# PA-HF_100W.net
KiCad netlist of a schematic drawn in Altium Designer
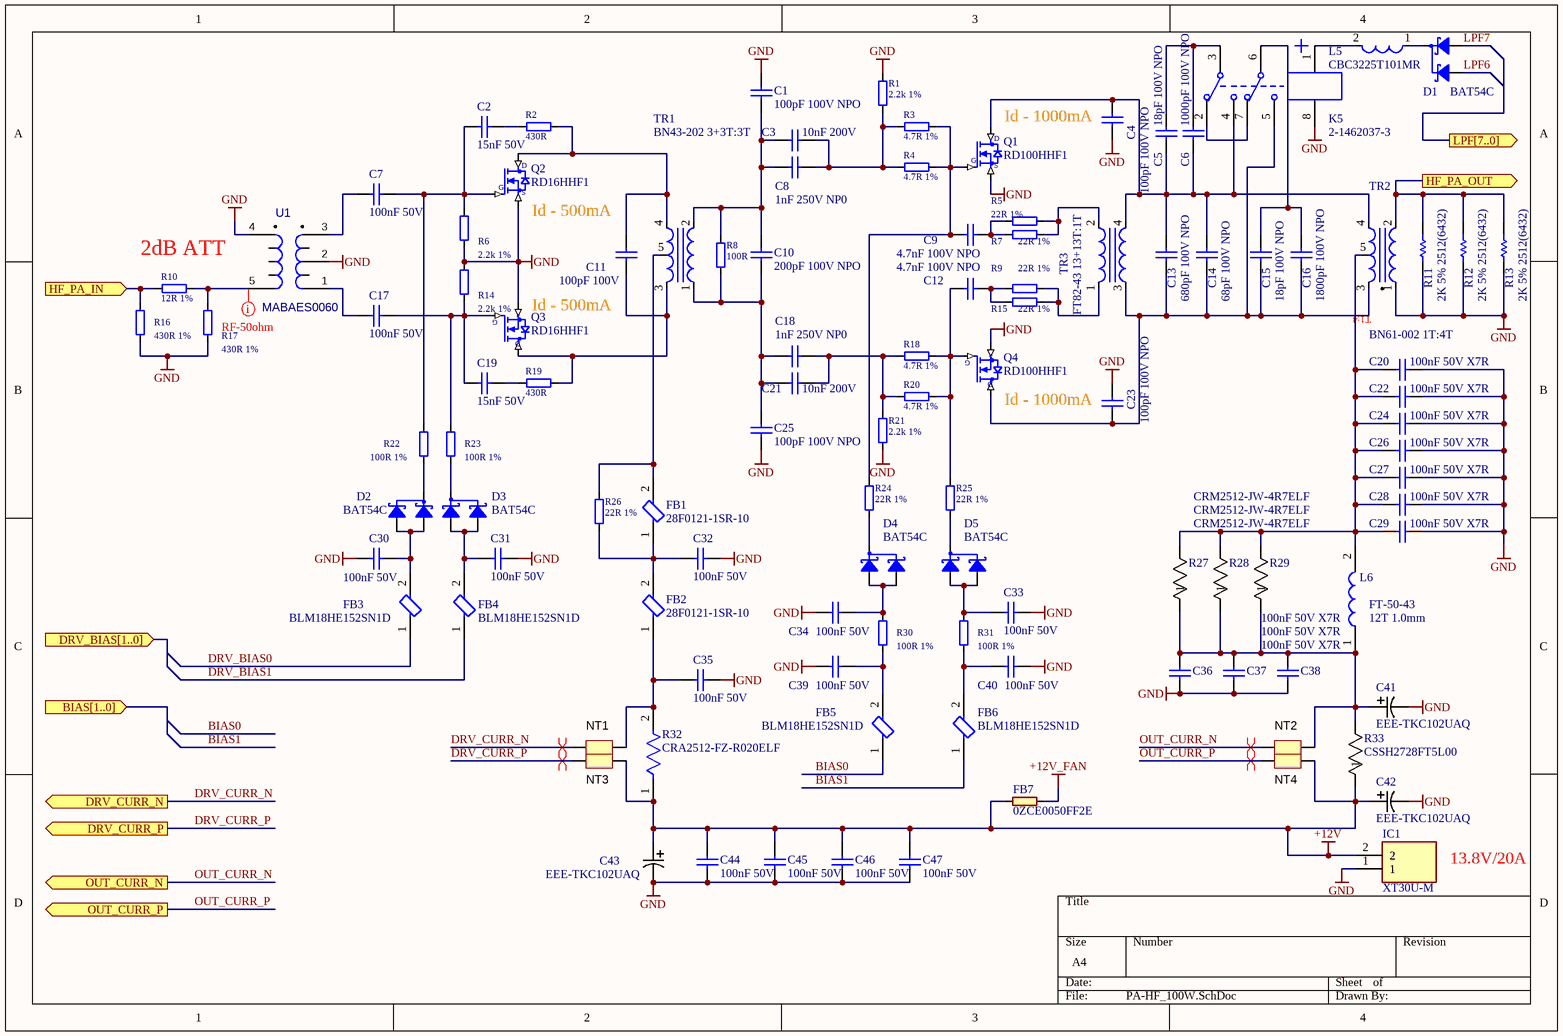
[diagram p0: PA-HF_100W.SchDoc]

(export (version "E")
  (design (tool "Eeschema 10.0.6"))
  (components
    (comp (ref "C1")
      (value "100pF 100V NPO")
      (footprint "C-1206")
      (description "Ceramic Multilayer Capacitor")
      (libsource (lib "Hristo") (part "C semi"))
    )
    (comp (ref "C2")
      (value "15nF 50V")
      (footprint "C-0805")
      (description "Ceramic Multilayer Capacitor")
      (libsource (lib "Hristo") (part "C semi"))
    )
    (comp (ref "C3")
      (value "10nF 200V")
      (footprint "C-1206")
      (description "Ceramic Multilayer Capacitor")
      (libsource (lib "Hristo") (part "C semi"))
    )
    (comp (ref "C4")
      (value "100pF 100V NPO")
      (footprint "C-1206")
      (description "Ceramic Multilayer Capacitor")
      (libsource (lib "Hristo") (part "C semi"))
    )
    (comp (ref "C5")
      (value "18pF 100V NPO")
      (footprint "C-1206")
      (description "Ceramic Multilayer Capacitor")
      (libsource (lib "Hristo") (part "C semi"))
    )
    (comp (ref "C6")
      (value "1000pF 100V NPO")
      (footprint "C-1206")
      (description "Ceramic Multilayer Capacitor")
      (libsource (lib "Hristo") (part "C semi"))
    )
    (comp (ref "C7")
      (value "100nF 50V")
      (footprint "C-0805")
      (description "Ceramic Multilayer Capacitor")
      (libsource (lib "Hristo") (part "C semi"))
    )
    (comp (ref "C8")
      (value "1nF 250V NP0")
      (footprint "C-1206")
      (description "Ceramic Multilayer Capacitor")
      (libsource (lib "Hristo") (part "C semi"))
    )
    (comp (ref "C9")
      (value "4.7nF 100V NPO")
      (footprint "C-1206")
      (description "Ceramic Multilayer Capacitor")
      (libsource (lib "Hristo") (part "C semi"))
    )
    (comp (ref "C10")
      (value "200pF 100V NPO")
      (footprint "C-1206")
      (description "Ceramic Multilayer Capacitor")
      (libsource (lib "Hristo") (part "C semi"))
    )
    (comp (ref "C11")
      (value "100pF 100V")
      (footprint "C-0805")
      (description "Ceramic Multilayer Capacitor")
      (libsource (lib "Hristo") (part "C semi"))
    )
    (comp (ref "C12")
      (value "4.7nF 100V NPO")
      (footprint "C-1206")
      (description "Ceramic Multilayer Capacitor")
      (libsource (lib "Hristo") (part "C semi"))
    )
    (comp (ref "C13")
      (value "680pF 100V NPO")
      (footprint "C-1206")
      (description "Ceramic Multilayer Capacitor")
      (libsource (lib "Hristo") (part "C semi"))
    )
    (comp (ref "C14")
      (value "68pF 100V NPO")
      (footprint "C-1206")
      (description "Ceramic Multilayer Capacitor")
      (libsource (lib "Hristo") (part "C semi"))
    )
    (comp (ref "C15")
      (value "18pF 100V NPO")
      (footprint "C-1206")
      (description "Ceramic Multilayer Capacitor")
      (libsource (lib "Hristo") (part "C semi"))
    )
    (comp (ref "C16")
      (value "1800pF 100V NPO")
      (footprint "C-1206")
      (description "Ceramic Multilayer Capacitor")
      (libsource (lib "Hristo") (part "C semi"))
    )
    (comp (ref "C17")
      (value "100nF 50V")
      (footprint "C-0805")
      (description "Ceramic Multilayer Capacitor")
      (libsource (lib "Hristo") (part "C semi"))
    )
    (comp (ref "C18")
      (value "1nF 250V NP0")
      (footprint "C-1206")
      (description "Ceramic Multilayer Capacitor")
      (libsource (lib "Hristo") (part "C semi"))
    )
    (comp (ref "C19")
      (value "15nF 50V")
      (footprint "C-0805")
      (description "Ceramic Multilayer Capacitor")
      (libsource (lib "Hristo") (part "C semi"))
    )
    (comp (ref "C20")
      (value "100nF 50V X7R")
      (footprint "C-1206")
      (description "Ceramic Multilayer Capacitor")
      (libsource (lib "Hristo") (part "C semi"))
    )
    (comp (ref "C21")
      (value "10nF 200V")
      (footprint "C-1206")
      (description "Ceramic Multilayer Capacitor")
      (libsource (lib "Hristo") (part "C semi"))
    )
    (comp (ref "C22")
      (value "100nF 50V X7R")
      (footprint "C-1206")
      (description "Ceramic Multilayer Capacitor")
      (libsource (lib "Hristo") (part "C semi"))
    )
    (comp (ref "C23")
      (value "100pF 100V NPO")
      (footprint "C-1206")
      (description "Ceramic Multilayer Capacitor")
      (libsource (lib "Hristo") (part "C semi"))
    )
    (comp (ref "C24")
      (value "100nF 50V X7R")
      (footprint "C-1206")
      (description "Ceramic Multilayer Capacitor")
      (libsource (lib "Hristo") (part "C semi"))
    )
    (comp (ref "C25")
      (value "100pF 100V NPO")
      (footprint "C-1206")
      (description "Ceramic Multilayer Capacitor")
      (libsource (lib "Hristo") (part "C semi"))
    )
    (comp (ref "C26")
      (value "100nF 50V X7R")
      (footprint "C-1206")
      (description "Ceramic Multilayer Capacitor")
      (libsource (lib "Hristo") (part "C semi"))
    )
    (comp (ref "C27")
      (value "100nF 50V X7R")
      (footprint "C-1206")
      (description "Ceramic Multilayer Capacitor")
      (libsource (lib "Hristo") (part "C semi"))
    )
    (comp (ref "C28")
      (value "100nF 50V X7R")
      (footprint "C-1206")
      (description "Ceramic Multilayer Capacitor")
      (libsource (lib "Hristo") (part "C semi"))
    )
    (comp (ref "C29")
      (value "100nF 50V X7R")
      (footprint "C-1206")
      (description "Ceramic Multilayer Capacitor")
      (libsource (lib "Hristo") (part "C semi"))
    )
    (comp (ref "C30")
      (value "100nF 50V")
      (footprint "C-0805")
      (description "Ceramic Multilayer Capacitor")
      (libsource (lib "Hristo") (part "C semi"))
    )
    (comp (ref "C31")
      (value "100nF 50V")
      (footprint "C-0805")
      (description "Ceramic Multilayer Capacitor")
      (libsource (lib "Hristo") (part "C semi"))
    )
    (comp (ref "C32")
      (value "100nF 50V")
      (footprint "C-0805")
      (description "Ceramic Multilayer Capacitor")
      (libsource (lib "Hristo") (part "C semi"))
    )
    (comp (ref "C33")
      (value "100nF 50V")
      (footprint "C-0805")
      (description "Ceramic Multilayer Capacitor")
      (libsource (lib "Hristo") (part "C semi"))
    )
    (comp (ref "C34")
      (value "100nF 50V")
      (footprint "C-0805")
      (description "Ceramic Multilayer Capacitor")
      (libsource (lib "Hristo") (part "C semi"))
    )
    (comp (ref "C35")
      (value "100nF 50V")
      (footprint "C-0805")
      (description "Ceramic Multilayer Capacitor")
      (libsource (lib "Hristo") (part "C semi"))
    )
    (comp (ref "C36")
      (value "100nF 50V X7R")
      (footprint "C-1206")
      (description "Ceramic Multilayer Capacitor")
      (libsource (lib "Hristo") (part "C semi"))
    )
    (comp (ref "C37")
      (value "100nF 50V X7R")
      (footprint "C-1206")
      (description "Ceramic Multilayer Capacitor")
      (libsource (lib "Hristo") (part "C semi"))
    )
    (comp (ref "C38")
      (value "100nF 50V X7R")
      (footprint "C-1206")
      (description "Ceramic Multilayer Capacitor")
      (libsource (lib "Hristo") (part "C semi"))
    )
    (comp (ref "C39")
      (value "100nF 50V")
      (footprint "C-0805")
      (description "Ceramic Multilayer Capacitor")
      (libsource (lib "Hristo") (part "C semi"))
    )
    (comp (ref "C40")
      (value "100nF 50V")
      (footprint "C-0805")
      (description "Ceramic Multilayer Capacitor")
      (libsource (lib "Hristo") (part "C semi"))
    )
    (comp (ref "C41")
      (value "EEE-TKC102UAQ")
      (footprint "CAP_PAN_EEE_H13_PAN")
      (description "No Description Available")
      (fields (field (name "COPYRIGHT") "Copyright (C) 2022 Ultra Librarian. All rights reserved."))
      (libsource (lib "Hristo") (part "EEE-TKC102UAQ"))
    )
    (comp (ref "C42")
      (value "EEE-TKC102UAQ")
      (footprint "CAP_PAN_EEE_H13_PAN")
      (description "No Description Available")
      (fields (field (name "COPYRIGHT") "Copyright (C) 2022 Ultra Librarian. All rights reserved."))
      (libsource (lib "Hristo") (part "EEE-TKC102UAQ"))
    )
    (comp (ref "C43")
      (value "EEE-TKC102UAQ")
      (footprint "CAP_PAN_EEE_H13_PAN")
      (description "No Description Available")
      (fields (field (name "COPYRIGHT") "Copyright (C) 2022 Ultra Librarian. All rights reserved."))
      (libsource (lib "Hristo") (part "EEE-TKC102UAQ"))
    )
    (comp (ref "C44")
      (value "100nF 50V")
      (footprint "C-0805")
      (description "Ceramic Multilayer Capacitor")
      (libsource (lib "Hristo") (part "C semi"))
    )
    (comp (ref "C45")
      (value "100nF 50V")
      (footprint "C-0805")
      (description "Ceramic Multilayer Capacitor")
      (libsource (lib "Hristo") (part "C semi"))
    )
    (comp (ref "C46")
      (value "100nF 50V")
      (footprint "C-0805")
      (description "Ceramic Multilayer Capacitor")
      (libsource (lib "Hristo") (part "C semi"))
    )
    (comp (ref "C47")
      (value "100nF 50V")
      (footprint "C-0805")
      (description "Ceramic Multilayer Capacitor")
      (libsource (lib "Hristo") (part "C semi"))
    )
    (comp (ref "D1")
      (value "BAT54C")
      (footprint "SOT-23")
      (description "Schottky barrier diodes")
      (fields (field (name "MANUFACTURER") "NXP"))
      (libsource (lib "EXP-SX Power R2.4") (part "D SH SOT23C"))
    )
    (comp (ref "D2")
      (value "BAT54C")
      (footprint "SOT-23")
      (description "Schottky barrier diodes")
      (fields (field (name "MANUFACTURER") "NXP"))
      (libsource (lib "EXP-SX Power R2.4") (part "D SH SOT23C"))
    )
    (comp (ref "D3")
      (value "BAT54C")
      (footprint "SOT-23")
      (description "Schottky barrier diodes")
      (fields (field (name "MANUFACTURER") "NXP"))
      (libsource (lib "EXP-SX Power R2.4") (part "D SH SOT23C"))
    )
    (comp (ref "D4")
      (value "BAT54C")
      (footprint "SOT-23")
      (description "Schottky barrier diodes")
      (fields (field (name "MANUFACTURER") "NXP"))
      (libsource (lib "EXP-SX Power R2.4") (part "D SH SOT23C"))
    )
    (comp (ref "D5")
      (value "BAT54C")
      (footprint "SOT-23")
      (description "Schottky barrier diodes")
      (fields (field (name "MANUFACTURER") "NXP"))
      (libsource (lib "EXP-SX Power R2.4") (part "D SH SOT23C"))
    )
    (comp (ref "FB1")
      (value "28F0121-1SR-10")
      (footprint "FP-28F0121-1SR-10-MFG")
      (description "FERRITE BEAD 96 OHM 2SMD 1LN")
      (libsource (lib "Altium Content Vault") (part "5f30dd21d616792df468990f7003faa"))
    )
    (comp (ref "FB2")
      (value "28F0121-1SR-10")
      (footprint "FP-28F0121-1SR-10-MFG")
      (description "FERRITE BEAD 96 OHM 2SMD 1LN")
      (libsource (lib "Altium Content Vault") (part "5f30dd21d616792df468990f7003faa"))
    )
    (comp (ref "FB3")
      (value "BLM18HE152SN1D")
      (footprint "FP-BLM18-0_15-t0_8-IPC_C")
      (description "Chip Ferrite Bead, 0603, 1500Ω @ 100MHz, 0.5Ω, 25%, 500mA")
      (fields (field (name "TOLERANCE") "25%"))
      (libsource (lib "Altium Content Vault") (part "5f30dd21d616792df468990f7003faa"))
    )
    (comp (ref "FB4")
      (value "BLM18HE152SN1D")
      (footprint "FP-BLM18-0_15-t0_8-IPC_C")
      (description "Chip Ferrite Bead, 0603, 1500Ω @ 100MHz, 0.5Ω, 25%, 500mA")
      (fields (field (name "TOLERANCE") "25%"))
      (libsource (lib "Altium Content Vault") (part "5f30dd21d616792df468990f7003faa"))
    )
    (comp (ref "FB5")
      (value "BLM18HE152SN1D")
      (footprint "FP-BLM18-0_15-t0_8-IPC_C")
      (description "Chip Ferrite Bead, 0603, 1500Ω @ 100MHz, 0.5Ω, 25%, 500mA")
      (fields (field (name "TOLERANCE") "25%"))
      (libsource (lib "Altium Content Vault") (part "5f30dd21d616792df468990f7003faa"))
    )
    (comp (ref "FB6")
      (value "BLM18HE152SN1D")
      (footprint "FP-BLM18-0_15-t0_8-IPC_C")
      (description "Chip Ferrite Bead, 0603, 1500Ω @ 100MHz, 0.5Ω, 25%, 500mA")
      (fields (field (name "TOLERANCE") "25%"))
      (libsource (lib "Altium Content Vault") (part "5f30dd21d616792df468990f7003faa"))
    )
    (comp (ref "FB7")
      (value "0ZCE0050FF2E")
      (footprint "C-0805")
      (description "Chip Ferrite Bead")
      (fields (field (name "MANUFACTURER") "KING CORE"))
      (libsource (lib "Hristo") (part "L BEAD SMD"))
    )
    (comp (ref "IC1")
      (value "XT30U-M")
      (footprint "SamacSys:XT30UM")
      (description "Integrated Circuit")
      (libsource (lib "*") (part "XT30U-M"))
    )
    (comp (ref "K5")
      (value "2-1462037-3")
      (footprint "TECO-2-1462037-3_V")
      (description "Signal Relay, 2 A, 12 VDC, -40 to 85 degC, 8-Pin SMD, RoHS, Tape and Reel")
      (fields (field (name "MANUFACTURER") "TE Connectivity"))
      (libsource (lib "Hristo") (part "CMP-2000-05409-1"))
    )
    (comp (ref "L5")
      (value "CBC3225T101MR")
      (footprint "FP-CB3225-MFG")
      (description "SMD Inductors 100uH ±20% 0.34A 1.82Ω 1210")
      (fields (field (name "TOLERANCE") "20%"))
      (libsource (lib "Altium Content Vault") (part "725321dda6339637d4d059423bc1c3c"))
    )
    (comp (ref "L6")
      (value "FT-50-43")
      (footprint "Amidon_FT50_43")
      (fields (field (name "ALTIUM_VALUE") "12T 1.0mm"))
      (libsource (lib "Hristo") (part "Amidon"))
    )
    (comp (ref "NT1")
      (value "Net-Tie")
      (footprint "Net-Tie_10mil")
      (description "Single point connection between nets.")
      (fields (field (name "SYMBOLCREATOR") "codlsc") (field (name "PUBLISHER") "Texas Instruments"))
      (libsource (lib "Hristo") (part "Net-Tie"))
    )
    (comp (ref "NT2")
      (value "Net-Tie")
      (footprint "Net-Tie_10mil")
      (description "Single point connection between nets.")
      (fields (field (name "SYMBOLCREATOR") "codlsc") (field (name "PUBLISHER") "Texas Instruments"))
      (libsource (lib "Hristo") (part "Net-Tie"))
    )
    (comp (ref "NT3")
      (value "Net-Tie")
      (footprint "Net-Tie_10mil")
      (description "Single point connection between nets.")
      (fields (field (name "SYMBOLCREATOR") "codlsc") (field (name "PUBLISHER") "Texas Instruments"))
      (libsource (lib "Hristo") (part "Net-Tie"))
    )
    (comp (ref "NT4")
      (value "Net-Tie")
      (footprint "Net-Tie_10mil")
      (description "Single point connection between nets.")
      (fields (field (name "SYMBOLCREATOR") "codlsc") (field (name "PUBLISHER") "Texas Instruments"))
      (libsource (lib "Hristo") (part "Net-Tie"))
    )
    (comp (ref "Q1")
      (value "RD100HHF1")
      (footprint "RD100HHF1")
      (libsource (lib "Hristo") (part "RD100HHF1"))
    )
    (comp (ref "Q2") (value "RD16HHF1") (footprint "RD16HHF1") (libsource (lib "Hristo") (part "RD16HHF1")))
    (comp (ref "Q3") (value "RD16HHF1") (footprint "RD16HHF1") (libsource (lib "Hristo") (part "RD16HHF1")))
    (comp (ref "Q4")
      (value "RD100HHF1")
      (footprint "RD100HHF1")
      (libsource (lib "Hristo") (part "RD100HHF1"))
    )
    (comp (ref "R1")
      (value "2.2k 1%")
      (footprint "R-1206")
      (description "Chip Resistor")
      (libsource (lib "Hristo") (part "RES semi"))
    )
    (comp (ref "R2")
      (value "430R")
      (footprint "R-1206")
      (description "Chip Resistor")
      (libsource (lib "Hristo") (part "RES semi"))
    )
    (comp (ref "R3")
      (value "4.7R 1%")
      (footprint "R-1206")
      (description "Chip Resistor")
      (libsource (lib "Hristo") (part "RES semi"))
    )
    (comp (ref "R4")
      (value "4.7R 1%")
      (footprint "R-1206")
      (description "Chip Resistor")
      (libsource (lib "Hristo") (part "RES semi"))
    )
    (comp (ref "R5")
      (value "22R 1%")
      (footprint "R-1206")
      (description "Chip Resistor")
      (libsource (lib "Hristo") (part "RES semi"))
    )
    (comp (ref "R6")
      (value "2.2k 1%")
      (footprint "R-0805")
      (description "Chip Resistor")
      (libsource (lib "Hristo") (part "RES semi"))
    )
    (comp (ref "R7")
      (value "22R 1%")
      (footprint "R-1206")
      (description "Chip Resistor")
      (libsource (lib "Hristo") (part "RES semi"))
    )
    (comp (ref "R8")
      (value "100R")
      (footprint "R-1206")
      (description "Chip Resistor")
      (libsource (lib "Hristo") (part "RES semi"))
    )
    (comp (ref "R9")
      (value "22R 1%")
      (footprint "R-1206")
      (description "Chip Resistor")
      (libsource (lib "Hristo") (part "RES semi"))
    )
    (comp (ref "R10")
      (value "12R 1%")
      (footprint "R-0805")
      (description "Chip Resistor")
      (libsource (lib "Hristo") (part "RES semi"))
    )
    (comp (ref "R11")
      (value "2K 5% 2512(6432)")
      (footprint "RESC2512(6432)_N")
      (description "2K 1W 5% 2512 (6432 Metric)  SMD")
      (fields (field (name "POWER") "1 W") (field (name "TOLERANCE") "5 %"))
      (libsource (lib "Altium Content Vault") (part "RES"))
    )
    (comp (ref "R12")
      (value "2K 5% 2512(6432)")
      (footprint "RESC2512(6432)_N")
      (description "2K 1W 5% 2512 (6432 Metric)  SMD")
      (fields (field (name "POWER") "1 W") (field (name "TOLERANCE") "5 %"))
      (libsource (lib "Altium Content Vault") (part "RES"))
    )
    (comp (ref "R13")
      (value "2K 5% 2512(6432)")
      (footprint "RESC2512(6432)_N")
      (description "2K 1W 5% 2512 (6432 Metric)  SMD")
      (fields (field (name "POWER") "1 W") (field (name "TOLERANCE") "5 %"))
      (libsource (lib "Altium Content Vault") (part "RES"))
    )
    (comp (ref "R14")
      (value "2.2k 1%")
      (footprint "R-0805")
      (description "Chip Resistor")
      (libsource (lib "Hristo") (part "RES semi"))
    )
    (comp (ref "R15")
      (value "22R 1%")
      (footprint "R-1206")
      (description "Chip Resistor")
      (libsource (lib "Hristo") (part "RES semi"))
    )
    (comp (ref "R16")
      (value "430R 1%")
      (footprint "R-0805")
      (description "Chip Resistor")
      (libsource (lib "Hristo") (part "RES semi"))
    )
    (comp (ref "R17")
      (value "430R 1%")
      (footprint "R-0805")
      (description "Chip Resistor")
      (libsource (lib "Hristo") (part "RES semi"))
    )
    (comp (ref "R18")
      (value "4.7R 1%")
      (footprint "R-1206")
      (description "Chip Resistor")
      (libsource (lib "Hristo") (part "RES semi"))
    )
    (comp (ref "R19")
      (value "430R")
      (footprint "R-1206")
      (description "Chip Resistor")
      (libsource (lib "Hristo") (part "RES semi"))
    )
    (comp (ref "R20")
      (value "4.7R 1%")
      (footprint "R-1206")
      (description "Chip Resistor")
      (libsource (lib "Hristo") (part "RES semi"))
    )
    (comp (ref "R21")
      (value "2.2k 1%")
      (footprint "R-1206")
      (description "Chip Resistor")
      (libsource (lib "Hristo") (part "RES semi"))
    )
    (comp (ref "R22")
      (value "100R 1%")
      (footprint "R-0805")
      (description "Chip Resistor")
      (libsource (lib "Hristo") (part "RES semi"))
    )
    (comp (ref "R23")
      (value "100R 1%")
      (footprint "R-0805")
      (description "Chip Resistor")
      (libsource (lib "Hristo") (part "RES semi"))
    )
    (comp (ref "R24")
      (value "22R 1%")
      (footprint "R-1206")
      (description "Chip Resistor")
      (libsource (lib "Hristo") (part "RES semi"))
    )
    (comp (ref "R25")
      (value "22R 1%")
      (footprint "R-1206")
      (description "Chip Resistor")
      (libsource (lib "Hristo") (part "RES semi"))
    )
    (comp (ref "R26")
      (value "22R 1%")
      (footprint "R-1206")
      (description "Chip Resistor")
      (libsource (lib "Hristo") (part "RES semi"))
    )
    (comp (ref "R27")
      (value "CRM2512-JW-4R7ELF")
      (footprint "BO_CR2512")
      (description "No Description Available")
      (fields (field (name "COPYRIGHT") "Copyright (C) 2022 Ultra Librarian. All rights reserved."))
      (libsource (lib "Hristo") (part "CRM2512-JW-4R7ELF"))
    )
    (comp (ref "R28")
      (value "CRM2512-JW-4R7ELF")
      (footprint "BO_CR2512")
      (description "No Description Available")
      (fields (field (name "COPYRIGHT") "Copyright (C) 2022 Ultra Librarian. All rights reserved."))
      (libsource (lib "Hristo") (part "CRM2512-JW-4R7ELF"))
    )
    (comp (ref "R29")
      (value "CRM2512-JW-4R7ELF")
      (footprint "BO_CR2512")
      (description "No Description Available")
      (fields (field (name "COPYRIGHT") "Copyright (C) 2022 Ultra Librarian. All rights reserved."))
      (libsource (lib "Hristo") (part "CRM2512-JW-4R7ELF"))
    )
    (comp (ref "R30")
      (value "100R 1%")
      (footprint "R-0805")
      (description "Chip Resistor")
      (libsource (lib "Hristo") (part "RES semi"))
    )
    (comp (ref "R31")
      (value "100R 1%")
      (footprint "R-0805")
      (description "Chip Resistor")
      (libsource (lib "Hristo") (part "RES semi"))
    )
    (comp (ref "R32")
      (value "CRA2512-FZ-R020ELF")
      (footprint "FP-CRA2512-IPC_C")
      (description "RES 0.02 OHM 1% 3W 2512")
      (libsource (lib "Altium Content Vault") (part "1029c3af85768c4190bb7ad29bc67b5"))
    )
    (comp (ref "R33")
      (value "CSSH2728FT5L00")
      (footprint "STA_CSSH2728_STP")
      (description "No Description Available")
      (fields (field (name "COPYRIGHT") "Copyright (C) 2022 Ultra Librarian. All rights reserved."))
      (libsource (lib "Hristo") (part "CSSH2728FT5L00"))
    )
    (comp (ref "TR1")
      (value "BN43-202 3+3T:3T")
      (footprint "BN43-202")
      (description "BN43-202 3+3T:3T 0.5mm")
      (libsource (lib "Sch") (part "BN43-202 3+3T{colon}3T"))
    )
    (comp (ref "TR2")
      (value "BN61-002 1T:4T")
      (footprint "BN61-002")
      (description "BN61-002 1T:4T 25ohms coaxial")
      (libsource (lib "Hristo") (part "BN61-002 1T{colon}4T"))
    )
    (comp (ref "TR3")
      (value "FT82-43 13+13T:1T")
      (footprint "Amidon_FT82-43")
      (description "BN43-202 3+3T:3T 0.5mm")
      (libsource (lib "Hristo") (part "FT82-43 13+13T{colon}1T"))
    )
    (comp (ref "U1")
      (value "MABAES0060")
      (footprint "TRANSF_ACORE2")
      (description "1:1")
      (libsource (lib "Hristo") (part "MABAES0060"))
    )
  )
  (nets
    (net (code "7") (name "+12V") (class "Default")
      (node (ref "C42") (pin "1") (pinfunction "1_1") (pintype "passive"))
      (node (ref "C43") (pin "1") (pinfunction "1_1") (pintype "passive"))
      (node (ref "C44") (pin "2") (pinfunction "2_2") (pintype "passive"))
      (node (ref "C45") (pin "2") (pinfunction "2_2") (pintype "passive"))
      (node (ref "C46") (pin "2") (pinfunction "2_2") (pintype "passive"))
      (node (ref "C47") (pin "2") (pinfunction "2_2") (pintype "passive"))
      (node (ref "FB7") (pin "1") (pinfunction "1_1") (pintype "passive"))
      (node (ref "IC1") (pin "2") (pinfunction "2_2") (pintype "passive"))
      (node (ref "NT3") (pin "2") (pinfunction "2_2") (pintype "passive"))
      (node (ref "NT4") (pin "2") (pinfunction "2_2") (pintype "passive"))
      (node (ref "R32") (pin "1") (pinfunction "1_1") (pintype "passive"))
      (node (ref "R33") (pin "1") (pinfunction "1_1") (pintype "passive"))
    )
    (net (code "8") (name "+12V_FAN") (class "Default")
      (node (ref "FB7") (pin "2") (pinfunction "2_2") (pintype "passive"))
    )
    (net (code "9") (name "/BIAS0") (class "Default")
      (node (ref "FB5") (pin "1") (pinfunction "1_1") (pintype "passive"))
    )
    (net (code "10") (name "/BIAS1") (class "Default")
      (node (ref "FB6") (pin "1") (pinfunction "1_1") (pintype "passive"))
    )
    (net (code "12") (name "/DRV_BIAS0") (class "Default")
      (node (ref "FB3") (pin "1") (pinfunction "1_1") (pintype "passive"))
    )
    (net (code "13") (name "/DRV_BIAS1") (class "Default")
      (node (ref "FB4") (pin "1") (pinfunction "1_1") (pintype "passive"))
    )
    (net (code "15") (name "/DRV_CURR_N") (class "Default")
      (node (ref "NT1") (pin "1") (pinfunction "1_1") (pintype "passive"))
    )
    (net (code "16") (name "/DRV_CURR_P") (class "Default")
      (node (ref "NT3") (pin "1") (pinfunction "1_1") (pintype "passive"))
    )
    (net (code "17") (name "/HF_PA_IN") (class "Default")
      (node (ref "R10") (pin "1") (pinfunction "1_1") (pintype "passive"))
      (node (ref "R16") (pin "2") (pinfunction "2_2") (pintype "passive"))
    )
    (net (code "18") (name "/HF_PA_OUT") (class "Default")
      (node (ref "R11") (pin "2") (pinfunction "2_2") (pintype "passive"))
      (node (ref "R12") (pin "2") (pinfunction "2_2") (pintype "passive"))
      (node (ref "R13") (pin "2") (pinfunction "2_2") (pintype "passive"))
      (node (ref "TR2") (pin "2") (pinfunction "2_2") (pintype "passive"))
    )
    (net (code "19") (name "/LPF6") (class "Default") (node (ref "D1") (pin "2") (pintype "passive")))
    (net (code "20") (name "/LPF7") (class "Default") (node (ref "D1") (pin "1") (pintype "passive")))
    (net (code "22") (name "/OUT_CURR_N") (class "Default")
      (node (ref "NT2") (pin "1") (pinfunction "1_1") (pintype "passive"))
    )
    (net (code "23") (name "/OUT_CURR_P") (class "Default")
      (node (ref "NT4") (pin "1") (pinfunction "1_1") (pintype "passive"))
    )
    (net (code "24") (name "GND") (class "Default")
      (node (ref "C1") (pin "1") (pinfunction "1_1") (pintype "passive"))
      (node (ref "C20") (pin "1") (pinfunction "1_1") (pintype "passive"))
      (node (ref "C22") (pin "1") (pinfunction "1_1") (pintype "passive"))
      (node (ref "C23") (pin "1") (pinfunction "1_1") (pintype "passive"))
      (node (ref "C24") (pin "1") (pinfunction "1_1") (pintype "passive"))
      (node (ref "C25") (pin "2") (pinfunction "2_2") (pintype "passive"))
      (node (ref "C26") (pin "1") (pinfunction "1_1") (pintype "passive"))
      (node (ref "C27") (pin "1") (pinfunction "1_1") (pintype "passive"))
      (node (ref "C28") (pin "1") (pinfunction "1_1") (pintype "passive"))
      (node (ref "C29") (pin "1") (pinfunction "1_1") (pintype "passive"))
      (node (ref "C30") (pin "2") (pinfunction "2_2") (pintype "passive"))
      (node (ref "C31") (pin "1") (pinfunction "1_1") (pintype "passive"))
      (node (ref "C32") (pin "1") (pinfunction "1_1") (pintype "passive"))
      (node (ref "C33") (pin "1") (pinfunction "1_1") (pintype "passive"))
      (node (ref "C34") (pin "1") (pinfunction "1_1") (pintype "passive"))
      (node (ref "C35") (pin "1") (pinfunction "1_1") (pintype "passive"))
      (node (ref "C36") (pin "1") (pinfunction "1_1") (pintype "passive"))
      (node (ref "C37") (pin "1") (pinfunction "1_1") (pintype "passive"))
      (node (ref "C38") (pin "1") (pinfunction "1_1") (pintype "passive"))
      (node (ref "C39") (pin "1") (pinfunction "1_1") (pintype "passive"))
      (node (ref "C4") (pin "2") (pinfunction "2_2") (pintype "passive"))
      (node (ref "C40") (pin "1") (pinfunction "1_1") (pintype "passive"))
      (node (ref "C41") (pin "2") (pinfunction "2_2") (pintype "passive"))
      (node (ref "C42") (pin "2") (pinfunction "2_2") (pintype "passive"))
      (node (ref "C43") (pin "2") (pinfunction "2_2") (pintype "passive"))
      (node (ref "C44") (pin "1") (pinfunction "1_1") (pintype "passive"))
      (node (ref "C45") (pin "1") (pinfunction "1_1") (pintype "passive"))
      (node (ref "C46") (pin "1") (pinfunction "1_1") (pintype "passive"))
      (node (ref "C47") (pin "1") (pinfunction "1_1") (pintype "passive"))
      (node (ref "IC1") (pin "1") (pinfunction "1_1") (pintype "passive"))
      (node (ref "K5") (pin "8") (pinfunction "8_8") (pintype "passive"))
      (node (ref "Q1") (pin "1") (pinfunction "S_1") (pintype "input"))
      (node (ref "Q2") (pin "1") (pinfunction "S_1") (pintype "input"))
      (node (ref "Q3") (pin "1") (pinfunction "S_1") (pintype "input"))
      (node (ref "Q4") (pin "1") (pinfunction "S_1") (pintype "input"))
      (node (ref "R1") (pin "2") (pinfunction "2_2") (pintype "passive"))
      (node (ref "R11") (pin "1") (pinfunction "1_1") (pintype "passive"))
      (node (ref "R12") (pin "1") (pinfunction "1_1") (pintype "passive"))
      (node (ref "R13") (pin "1") (pinfunction "1_1") (pintype "passive"))
      (node (ref "R14") (pin "2") (pinfunction "2_2") (pintype "passive"))
      (node (ref "R16") (pin "1") (pinfunction "1_1") (pintype "passive"))
      (node (ref "R17") (pin "1") (pinfunction "1_1") (pintype "passive"))
      (node (ref "R21") (pin "2") (pinfunction "2_2") (pintype "passive"))
      (node (ref "R6") (pin "1") (pinfunction "1_1") (pintype "passive"))
      (node (ref "TR2") (pin "1") (pinfunction "1_1") (pintype "passive"))
      (node (ref "U1") (pin "2") (pinfunction "S2_2") (pintype "passive"))
      (node (ref "U1") (pin "4") (pinfunction "P1_4") (pintype "passive"))
    )
    (net (code "25") (name "Net-(C1-Pad2)") (class "Default")
      (node (ref "C1") (pin "2") (pinfunction "2_2") (pintype "passive"))
      (node (ref "C10") (pin "1") (pinfunction "1_1") (pintype "passive"))
      (node (ref "C3") (pin "1") (pinfunction "1_1") (pintype "passive"))
      (node (ref "C8") (pin "1") (pinfunction "1_1") (pintype "passive"))
      (node (ref "R8") (pin "2") (pinfunction "2_2") (pintype "passive"))
      (node (ref "TR1") (pin "2") (pinfunction "2_2") (pintype "passive"))
    )
    (net (code "26") (name "Net-(C2-Pad1)") (class "Default")
      (node (ref "C2") (pin "1") (pinfunction "1_1") (pintype "passive"))
      (node (ref "C7") (pin "2") (pinfunction "2_2") (pintype "passive"))
      (node (ref "Q2") (pin "2") (pintype "input"))
      (node (ref "R22") (pin "2") (pinfunction "2_2") (pintype "passive"))
      (node (ref "R6") (pin "2") (pinfunction "2_2") (pintype "passive"))
    )
    (net (code "27") (name "Net-(C2-Pad2)") (class "Default")
      (node (ref "C2") (pin "2") (pinfunction "2_2") (pintype "passive"))
      (node (ref "R2") (pin "1") (pinfunction "1_1") (pintype "passive"))
    )
    (net (code "28") (name "Net-(C3-Pad2)") (class "Default")
      (node (ref "C3") (pin "2") (pinfunction "2_2") (pintype "passive"))
      (node (ref "C8") (pin "2") (pinfunction "2_2") (pintype "passive"))
      (node (ref "R1") (pin "1") (pinfunction "1_1") (pintype "passive"))
      (node (ref "R3") (pin "1") (pinfunction "1_1") (pintype "passive"))
      (node (ref "R4") (pin "1") (pinfunction "1_1") (pintype "passive"))
    )
    (net (code "29") (name "Net-(C5-Pad2)") (class "Default")
      (node (ref "C5") (pin "2") (pinfunction "2_2") (pintype "passive"))
      (node (ref "C6") (pin "2") (pinfunction "2_2") (pintype "passive"))
      (node (ref "K5") (pin "3") (pinfunction "3_3") (pintype "passive"))
    )
    (net (code "30") (name "Net-(C9-Pad1)") (class "Default")
      (node (ref "C9") (pin "1") (pinfunction "1_1") (pintype "passive"))
      (node (ref "Q1") (pin "2") (pintype "input"))
      (node (ref "R24") (pin "2") (pinfunction "2_2") (pintype "passive"))
      (node (ref "R3") (pin "2") (pinfunction "2_2") (pintype "passive"))
      (node (ref "R4") (pin "2") (pinfunction "2_2") (pintype "passive"))
    )
    (net (code "31") (name "Net-(C9-Pad2)") (class "Default")
      (node (ref "C9") (pin "2") (pinfunction "2_2") (pintype "passive"))
      (node (ref "R5") (pin "1") (pinfunction "1_1") (pintype "passive"))
      (node (ref "R7") (pin "1") (pinfunction "1_1") (pintype "passive"))
    )
    (net (code "32") (name "Net-(C10-Pad2)") (class "Default")
      (node (ref "C10") (pin "2") (pinfunction "2_2") (pintype "passive"))
      (node (ref "C18") (pin "1") (pinfunction "1_1") (pintype "passive"))
      (node (ref "C21") (pin "1") (pinfunction "1_1") (pintype "passive"))
      (node (ref "C25") (pin "1") (pinfunction "1_1") (pintype "passive"))
      (node (ref "R8") (pin "1") (pinfunction "1_1") (pintype "passive"))
      (node (ref "TR1") (pin "1") (pinfunction "1_1") (pintype "passive"))
    )
    (net (code "33") (name "Net-(C12-Pad1)") (class "Default")
      (node (ref "C12") (pin "1") (pinfunction "1_1") (pintype "passive"))
      (node (ref "Q4") (pin "2") (pintype "input"))
      (node (ref "R18") (pin "2") (pinfunction "2_2") (pintype "passive"))
      (node (ref "R20") (pin "2") (pinfunction "2_2") (pintype "passive"))
      (node (ref "R25") (pin "2") (pinfunction "2_2") (pintype "passive"))
    )
    (net (code "34") (name "Net-(C12-Pad2)") (class "Default")
      (node (ref "C12") (pin "2") (pinfunction "2_2") (pintype "passive"))
      (node (ref "R15") (pin "1") (pinfunction "1_1") (pintype "passive"))
      (node (ref "R9") (pin "1") (pinfunction "1_1") (pintype "passive"))
    )
    (net (code "35") (name "Net-(C15-Pad2)") (class "Default")
      (node (ref "C15") (pin "2") (pinfunction "2_2") (pintype "passive"))
      (node (ref "C16") (pin "1") (pinfunction "1_1") (pintype "passive"))
      (node (ref "K5") (pin "6") (pinfunction "6_6") (pintype "passive"))
    )
    (net (code "36") (name "Net-(C17-Pad2)") (class "Default")
      (node (ref "C17") (pin "2") (pinfunction "2_2") (pintype "passive"))
      (node (ref "C19") (pin "1") (pinfunction "1_1") (pintype "passive"))
      (node (ref "Q3") (pin "2") (pintype "input"))
      (node (ref "R14") (pin "1") (pinfunction "1_1") (pintype "passive"))
      (node (ref "R23") (pin "2") (pinfunction "2_2") (pintype "passive"))
    )
    (net (code "37") (name "Net-(C18-Pad2)") (class "Default")
      (node (ref "C18") (pin "2") (pinfunction "2_2") (pintype "passive"))
      (node (ref "C21") (pin "2") (pinfunction "2_2") (pintype "passive"))
      (node (ref "R18") (pin "1") (pinfunction "1_1") (pintype "passive"))
      (node (ref "R20") (pin "1") (pinfunction "1_1") (pintype "passive"))
      (node (ref "R21") (pin "1") (pinfunction "1_1") (pintype "passive"))
    )
    (net (code "38") (name "Net-(C19-Pad2)") (class "Default")
      (node (ref "C19") (pin "2") (pinfunction "2_2") (pintype "passive"))
      (node (ref "R19") (pin "1") (pinfunction "1_1") (pintype "passive"))
    )
    (net (code "39") (name "Net-(C20-Pad2)") (class "Default")
      (node (ref "C20") (pin "2") (pinfunction "2_2") (pintype "passive"))
      (node (ref "C22") (pin "2") (pinfunction "2_2") (pintype "passive"))
      (node (ref "C24") (pin "2") (pinfunction "2_2") (pintype "passive"))
      (node (ref "C26") (pin "2") (pinfunction "2_2") (pintype "passive"))
      (node (ref "C27") (pin "2") (pinfunction "2_2") (pintype "passive"))
      (node (ref "C28") (pin "2") (pinfunction "2_2") (pintype "passive"))
      (node (ref "C29") (pin "2") (pinfunction "2_2") (pintype "passive"))
      (node (ref "L6") (pin "2") (pinfunction "2_2") (pintype "passive"))
      (node (ref "R27") (pin "2") (pinfunction "2_2") (pintype "passive"))
      (node (ref "R28") (pin "2") (pinfunction "2_2") (pintype "passive"))
      (node (ref "R29") (pin "2") (pinfunction "2_2") (pintype "passive"))
      (node (ref "TR2") (pin "5") (pinfunction "5_5") (pintype "passive"))
    )
    (net (code "40") (name "Net-(C30-Pad1)") (class "Default")
      (node (ref "C30") (pin "1") (pinfunction "1_1") (pintype "passive"))
      (node (ref "D2") (pin "1") (pintype "passive"))
      (node (ref "D2") (pin "2") (pintype "passive"))
      (node (ref "FB3") (pin "2") (pinfunction "2_2") (pintype "passive"))
    )
    (net (code "41") (name "Net-(C31-Pad2)") (class "Default")
      (node (ref "C31") (pin "2") (pinfunction "2_2") (pintype "passive"))
      (node (ref "D3") (pin "1") (pintype "passive"))
      (node (ref "D3") (pin "2") (pintype "passive"))
      (node (ref "FB4") (pin "2") (pinfunction "2_2") (pintype "passive"))
    )
    (net (code "42") (name "Net-(C32-Pad2)") (class "Default")
      (node (ref "C32") (pin "2") (pinfunction "2_2") (pintype "passive"))
      (node (ref "FB1") (pin "1") (pinfunction "1_1") (pintype "passive"))
      (node (ref "FB2") (pin "2") (pinfunction "2_2") (pintype "passive"))
      (node (ref "R26") (pin "1") (pinfunction "1_1") (pintype "passive"))
    )
    (net (code "43") (name "Net-(C33-Pad2)") (class "Default")
      (node (ref "C33") (pin "2") (pinfunction "2_2") (pintype "passive"))
      (node (ref "D5") (pin "1") (pintype "passive"))
      (node (ref "D5") (pin "2") (pintype "passive"))
      (node (ref "R31") (pin "2") (pinfunction "2_2") (pintype "passive"))
    )
    (net (code "44") (name "Net-(C34-Pad2)") (class "Default")
      (node (ref "C34") (pin "2") (pinfunction "2_2") (pintype "passive"))
      (node (ref "D4") (pin "1") (pintype "passive"))
      (node (ref "D4") (pin "2") (pintype "passive"))
      (node (ref "R30") (pin "2") (pinfunction "2_2") (pintype "passive"))
    )
    (net (code "45") (name "Net-(C35-Pad2)") (class "Default")
      (node (ref "C35") (pin "2") (pinfunction "2_2") (pintype "passive"))
      (node (ref "FB2") (pin "1") (pinfunction "1_1") (pintype "passive"))
      (node (ref "NT1") (pin "2") (pinfunction "2_2") (pintype "passive"))
      (node (ref "R32") (pin "2") (pinfunction "2_2") (pintype "passive"))
    )
    (net (code "46") (name "Net-(C36-Pad2)") (class "Default")
      (node (ref "C36") (pin "2") (pinfunction "2_2") (pintype "passive"))
      (node (ref "C37") (pin "2") (pinfunction "2_2") (pintype "passive"))
      (node (ref "C38") (pin "2") (pinfunction "2_2") (pintype "passive"))
      (node (ref "C41") (pin "1") (pinfunction "1_1") (pintype "passive"))
      (node (ref "L6") (pin "1") (pinfunction "1_1") (pintype "passive"))
      (node (ref "NT2") (pin "2") (pinfunction "2_2") (pintype "passive"))
      (node (ref "R27") (pin "1") (pinfunction "1_1") (pintype "passive"))
      (node (ref "R28") (pin "1") (pinfunction "1_1") (pintype "passive"))
      (node (ref "R29") (pin "1") (pinfunction "1_1") (pintype "passive"))
      (node (ref "R33") (pin "2") (pinfunction "2_2") (pintype "passive"))
    )
    (net (code "47") (name "Net-(C39-Pad2)") (class "Default")
      (node (ref "C39") (pin "2") (pinfunction "2_2") (pintype "passive"))
      (node (ref "FB5") (pin "2") (pinfunction "2_2") (pintype "passive"))
      (node (ref "R30") (pin "1") (pinfunction "1_1") (pintype "passive"))
    )
    (net (code "48") (name "Net-(C40-Pad2)") (class "Default")
      (node (ref "C40") (pin "2") (pinfunction "2_2") (pintype "passive"))
      (node (ref "FB6") (pin "2") (pinfunction "2_2") (pintype "passive"))
      (node (ref "R31") (pin "1") (pinfunction "1_1") (pintype "passive"))
    )
    (net (code "49") (name "Net-(D1-Pad3)") (class "Default")
      (node (ref "D1") (pin "3") (pintype "passive"))
      (node (ref "L5") (pin "1") (pinfunction "1_1") (pintype "passive"))
    )
    (net (code "50") (name "Net-(D2-Pad3)") (class "Default")
      (node (ref "D2") (pin "3") (pintype "passive"))
      (node (ref "R22") (pin "1") (pinfunction "1_1") (pintype "passive"))
    )
    (net (code "51") (name "Net-(D3-Pad3)") (class "Default")
      (node (ref "D3") (pin "3") (pintype "passive"))
      (node (ref "R23") (pin "1") (pinfunction "1_1") (pintype "passive"))
    )
    (net (code "52") (name "Net-(D4-Pad3)") (class "Default")
      (node (ref "D4") (pin "3") (pintype "passive"))
      (node (ref "R24") (pin "1") (pinfunction "1_1") (pintype "passive"))
    )
    (net (code "53") (name "Net-(D5-Pad3)") (class "Default")
      (node (ref "D5") (pin "3") (pintype "passive"))
      (node (ref "R25") (pin "1") (pinfunction "1_1") (pintype "passive"))
    )
    (net (code "54") (name "Net-(FB1-Pad2)") (class "Default")
      (node (ref "FB1") (pin "2") (pinfunction "2_2") (pintype "passive"))
      (node (ref "R26") (pin "2") (pinfunction "2_2") (pintype "passive"))
      (node (ref "TR1") (pin "5") (pinfunction "5_5") (pintype "passive"))
    )
    (net (code "55") (name "Net-(K5-Pad1)") (class "Default")
      (node (ref "K5") (pin "1") (pinfunction "1_1") (pintype "passive"))
      (node (ref "L5") (pin "2") (pinfunction "2_2") (pintype "passive"))
    )
    (net (code "56") (name "Net-(K5-Pad2)") (class "Default")
      (node (ref "K5") (pin "2") (pinfunction "2_2") (pintype "passive"))
      (node (ref "K5") (pin "7") (pinfunction "7_7") (pintype "passive"))
    )
    (net (code "57") (name "Net-(Q1-D)") (class "Default")
      (node (ref "C13") (pin "1") (pinfunction "1_1") (pintype "passive"))
      (node (ref "C14") (pin "1") (pinfunction "1_1") (pintype "passive"))
      (node (ref "C4") (pin "1") (pinfunction "1_1") (pintype "passive"))
      (node (ref "C5") (pin "1") (pinfunction "1_1") (pintype "passive"))
      (node (ref "C6") (pin "1") (pinfunction "1_1") (pintype "passive"))
      (node (ref "K5") (pin "4") (pinfunction "4_4") (pintype "passive"))
      (node (ref "Q1") (pin "3") (pinfunction "D_3") (pintype "input"))
      (node (ref "TR2") (pin "4") (pinfunction "4_4") (pintype "passive"))
      (node (ref "TR3") (pin "4") (pinfunction "4_4") (pintype "passive"))
    )
    (net (code "58") (name "Net-(Q2-D)") (class "Default")
      (node (ref "C11") (pin "2") (pinfunction "2_2") (pintype "passive"))
      (node (ref "Q2") (pin "3") (pinfunction "D_3") (pintype "input"))
      (node (ref "R2") (pin "2") (pinfunction "2_2") (pintype "passive"))
      (node (ref "TR1") (pin "4") (pinfunction "4_4") (pintype "passive"))
    )
    (net (code "59") (name "Net-(Q3-D)") (class "Default")
      (node (ref "C11") (pin "1") (pinfunction "1_1") (pintype "passive"))
      (node (ref "Q3") (pin "3") (pinfunction "D_3") (pintype "input"))
      (node (ref "R19") (pin "2") (pinfunction "2_2") (pintype "passive"))
      (node (ref "TR1") (pin "3") (pinfunction "3_3") (pintype "passive"))
    )
    (net (code "60") (name "Net-(Q4-D)") (class "Default")
      (node (ref "C13") (pin "2") (pinfunction "2_2") (pintype "passive"))
      (node (ref "C14") (pin "2") (pinfunction "2_2") (pintype "passive"))
      (node (ref "C15") (pin "1") (pinfunction "1_1") (pintype "passive"))
      (node (ref "C16") (pin "2") (pinfunction "2_2") (pintype "passive"))
      (node (ref "C23") (pin "2") (pinfunction "2_2") (pintype "passive"))
      (node (ref "K5") (pin "5") (pinfunction "5_5") (pintype "passive"))
      (node (ref "Q4") (pin "3") (pinfunction "D_3") (pintype "input"))
      (node (ref "TR2") (pin "3") (pinfunction "3_3") (pintype "passive"))
      (node (ref "TR3") (pin "3") (pinfunction "3_3") (pintype "passive"))
    )
    (net (code "61") (name "Net-(R5-Pad2)") (class "Default")
      (node (ref "R5") (pin "2") (pinfunction "2_2") (pintype "passive"))
      (node (ref "R7") (pin "2") (pinfunction "2_2") (pintype "passive"))
      (node (ref "TR3") (pin "2") (pinfunction "2_2") (pintype "passive"))
    )
    (net (code "62") (name "Net-(R15-Pad2)") (class "Default")
      (node (ref "R15") (pin "2") (pinfunction "2_2") (pintype "passive"))
      (node (ref "R9") (pin "2") (pinfunction "2_2") (pintype "passive"))
      (node (ref "TR3") (pin "1") (pinfunction "1_1") (pintype "passive"))
    )
    (net (code "63") (name "Net-(U1-P2)") (class "Default")
      (node (ref "R10") (pin "2") (pinfunction "2_2") (pintype "passive"))
      (node (ref "R17") (pin "2") (pinfunction "2_2") (pintype "passive"))
      (node (ref "U1") (pin "5") (pinfunction "P2_5") (pintype "passive"))
    )
    (net (code "64") (name "Net-(U1-S1)") (class "Default")
      (node (ref "C7") (pin "1") (pinfunction "1_1") (pintype "passive"))
      (node (ref "U1") (pin "3") (pinfunction "S1_3") (pintype "passive"))
    )
    (net (code "65") (name "Net-(U1-S3)") (class "Default")
      (node (ref "C17") (pin "1") (pinfunction "1_1") (pintype "passive"))
      (node (ref "U1") (pin "1") (pinfunction "S3_1") (pintype "passive"))
    )
  )
)
